# AD.net
KiCad netlist of a schematic drawn in Altium Designer
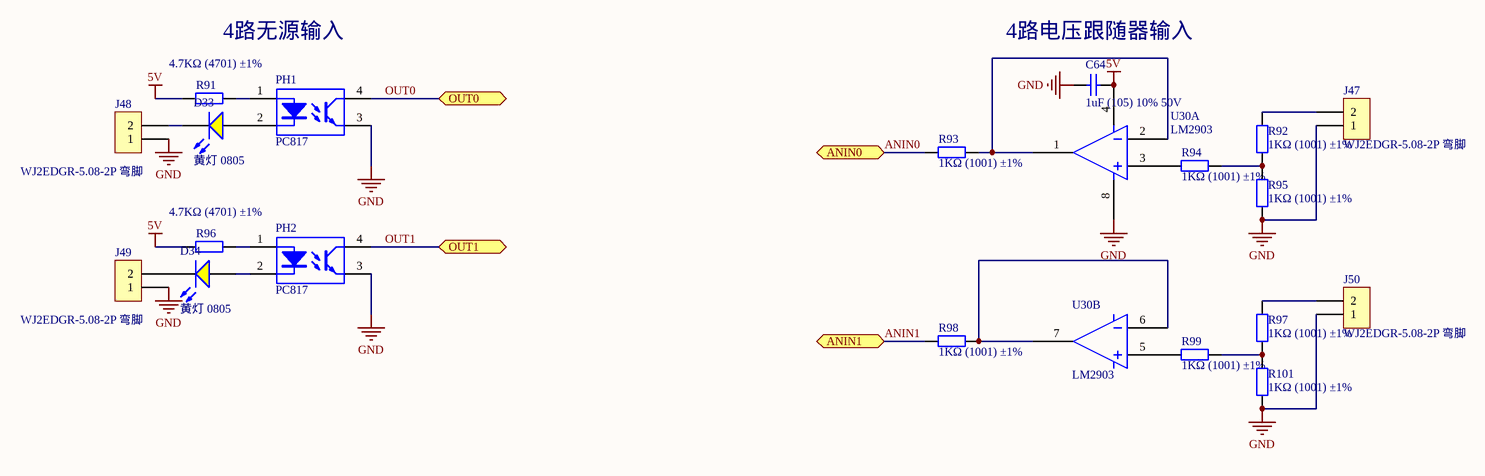
[diagram p0: 光耦输入&AD输入.SchDoc]

(export (version "E")
  (design (tool "Eeschema 10.0.6"))
  (components
    (comp (ref "C64")
      (value "1uF (105) 10% 50V")
      (footprint "0805_C")
      (description "贴片电容")
      (libsource (lib "Cap") (part "0805 1uF (105) 10% 50V"))
    )
    (comp (ref "D33")
      (value "黄灯 0805")
      (footprint "0805_LED_S1")
      (description "发光二极管")
      (libsource (lib "LED") (part "0805 黄灯"))
    )
    (comp (ref "D34")
      (value "黄灯 0805")
      (footprint "0805_LED_S1")
      (description "发光二极管")
      (libsource (lib "LED") (part "0805 黄灯"))
    )
    (comp (ref "J47")
      (value "WJ2EDGR-5.08-2P 弯脚")
      (footprint "Connector:WJ2EDGR-5.08-2")
      (description "2EDG连接器")
      (libsource (lib "Connector") (part "WJ2EDGR-5.08-2P 弯脚"))
    )
    (comp (ref "J48")
      (value "WJ2EDGR-5.08-2P 弯脚")
      (footprint "Connector:WJ2EDGR-5.08-2")
      (description "2EDG连接器")
      (libsource (lib "") (part "WJ2EDGR-5.08-2P 弯脚_1"))
    )
    (comp (ref "J49")
      (value "WJ2EDGR-5.08-2P 弯脚")
      (footprint "Connector:WJ2EDGR-5.08-2")
      (description "2EDG连接器")
      (libsource (lib "") (part "WJ2EDGR-5.08-2P 弯脚_1"))
    )
    (comp (ref "J50")
      (value "WJ2EDGR-5.08-2P 弯脚")
      (footprint "Connector:WJ2EDGR-5.08-2")
      (description "2EDG连接器")
      (libsource (lib "Connector") (part "WJ2EDGR-5.08-2P 弯脚"))
    )
    (comp (ref "PH1")
      (value "PC817")
      (footprint "SOP-4_P2.54")
      (description "Optoisolator")
      (libsource (lib "淘宝封装") (part "PC817"))
    )
    (comp (ref "PH2")
      (value "PC817")
      (footprint "SOP-4_P2.54")
      (description "Optoisolator")
      (libsource (lib "淘宝封装") (part "PC817"))
    )
    (comp (ref "R91")
      (value "4.7KΩ (4701) ±1%")
      (footprint "0805_R")
      (description "贴片电阻")
      (libsource (lib "RES") (part "0805 4.7KΩ (4701) 1%"))
    )
    (comp (ref "R92")
      (value "1KΩ (1001) ±1%")
      (footprint "0805_R")
      (description "贴片电阻")
      (libsource (lib "") (part "0805 1KΩ (1001) 1%_1"))
    )
    (comp (ref "R93")
      (value "1KΩ (1001) ±1%")
      (footprint "0805_R")
      (description "贴片电阻")
      (libsource (lib "RES") (part "0805 1KΩ (1001) 1%"))
    )
    (comp (ref "R94")
      (value "1KΩ (1001) ±1%")
      (footprint "0805_R")
      (description "贴片电阻")
      (libsource (lib "RES") (part "0805 1KΩ (1001) 1%"))
    )
    (comp (ref "R95")
      (value "1KΩ (1001) ±1%")
      (footprint "0805_R")
      (description "贴片电阻")
      (libsource (lib "") (part "0805 1KΩ (1001) 1%_1"))
    )
    (comp (ref "R96")
      (value "4.7KΩ (4701) ±1%")
      (footprint "0805_R")
      (description "贴片电阻")
      (libsource (lib "RES") (part "0805 4.7KΩ (4701) 1%"))
    )
    (comp (ref "R97")
      (value "1KΩ (1001) ±1%")
      (footprint "0805_R")
      (description "贴片电阻")
      (libsource (lib "") (part "0805 1KΩ (1001) 1%_1"))
    )
    (comp (ref "R98")
      (value "1KΩ (1001) ±1%")
      (footprint "0805_R")
      (description "贴片电阻")
      (libsource (lib "RES") (part "0805 1KΩ (1001) 1%"))
    )
    (comp (ref "R99")
      (value "1KΩ (1001) ±1%")
      (footprint "0805_R")
      (description "贴片电阻")
      (libsource (lib "RES") (part "0805 1KΩ (1001) 1%"))
    )
    (comp (ref "R101")
      (value "1KΩ (1001) ±1%")
      (footprint "0805_R")
      (description "贴片电阻")
      (libsource (lib "") (part "0805 1KΩ (1001) 1%_1"))
    )
    (comp (ref "U30") (value "LM2903") (footprint "SOP-8") (libsource (lib "*") (part "LM193")))
  )
  (nets
    (net (code "1") (name "/ANIN0") (class "Default")
      (node (ref "R93") (pin "2") (pinfunction "2_2") (pintype "passive"))
    )
    (net (code "2") (name "/ANIN1") (class "Default")
      (node (ref "R98") (pin "2") (pinfunction "2_2") (pintype "passive"))
    )
    (net (code "3") (name "/OUT0") (class "Default")
      (node (ref "PH1") (pin "4") (pinfunction "C_4") (pintype "passive"))
    )
    (net (code "4") (name "/OUT1") (class "Default")
      (node (ref "PH2") (pin "4") (pinfunction "C_4") (pintype "passive"))
    )
    (net (code "5") (name "5V") (class "Default")
      (node (ref "C64") (pin "2") (pinfunction "2_2") (pintype "passive"))
      (node (ref "R91") (pin "1") (pinfunction "1_1") (pintype "passive"))
      (node (ref "R96") (pin "1") (pinfunction "1_1") (pintype "passive"))
      (node (ref "U30") (pin "4") (pintype "passive"))
    )
    (net (code "6") (name "GND") (class "Default")
      (node (ref "C64") (pin "1") (pinfunction "1_1") (pintype "passive"))
      (node (ref "J47") (pin "1") (pinfunction "1_1") (pintype "passive"))
      (node (ref "J48") (pin "1") (pinfunction "1_1") (pintype "passive"))
      (node (ref "J49") (pin "1") (pinfunction "1_1") (pintype "passive"))
      (node (ref "J50") (pin "1") (pinfunction "1_1") (pintype "passive"))
      (node (ref "PH1") (pin "3") (pinfunction "E_3") (pintype "passive"))
      (node (ref "PH2") (pin "3") (pinfunction "E_3") (pintype "passive"))
      (node (ref "R101") (pin "1") (pinfunction "1_1") (pintype "passive"))
      (node (ref "R95") (pin "1") (pinfunction "1_1") (pintype "passive"))
      (node (ref "U30") (pin "8") (pintype "passive"))
    )
    (net (code "7") (name "Net-(D33-PadK)") (class "Default")
      (node (ref "D33") (pin "K") (pinfunction "K_K") (pintype "passive"))
      (node (ref "J48") (pin "2") (pinfunction "2_2") (pintype "passive"))
    )
    (net (code "8") (name "Net-(D34-PadK)") (class "Default")
      (node (ref "D34") (pin "K") (pinfunction "K_K") (pintype "passive"))
      (node (ref "J49") (pin "2") (pinfunction "2_2") (pintype "passive"))
    )
    (net (code "9") (name "Net-(J47-Pad2)") (class "Default")
      (node (ref "J47") (pin "2") (pinfunction "2_2") (pintype "passive"))
      (node (ref "R92") (pin "2") (pinfunction "2_2") (pintype "passive"))
    )
    (net (code "10") (name "Net-(J50-Pad2)") (class "Default")
      (node (ref "J50") (pin "2") (pinfunction "2_2") (pintype "passive"))
      (node (ref "R97") (pin "2") (pinfunction "2_2") (pintype "passive"))
    )
    (net (code "11") (name "Net-(PH1-A)") (class "Default")
      (node (ref "PH1") (pin "1") (pinfunction "A_1") (pintype "passive"))
      (node (ref "R91") (pin "2") (pinfunction "2_2") (pintype "passive"))
    )
    (net (code "12") (name "Net-(PH1-K)") (class "Default")
      (node (ref "D33") (pin "A") (pinfunction "A_A") (pintype "passive"))
      (node (ref "PH1") (pin "2") (pinfunction "K_2") (pintype "passive"))
    )
    (net (code "13") (name "Net-(PH2-A)") (class "Default")
      (node (ref "PH2") (pin "1") (pinfunction "A_1") (pintype "passive"))
      (node (ref "R96") (pin "2") (pinfunction "2_2") (pintype "passive"))
    )
    (net (code "14") (name "Net-(PH2-K)") (class "Default")
      (node (ref "D34") (pin "A") (pinfunction "A_A") (pintype "passive"))
      (node (ref "PH2") (pin "2") (pinfunction "K_2") (pintype "passive"))
    )
    (net (code "15") (name "Net-(R92-Pad1)") (class "Default")
      (node (ref "R92") (pin "1") (pinfunction "1_1") (pintype "passive"))
      (node (ref "R94") (pin "1") (pinfunction "1_1") (pintype "passive"))
      (node (ref "R95") (pin "2") (pinfunction "2_2") (pintype "passive"))
    )
    (net (code "16") (name "Net-(R93-Pad1)") (class "Default")
      (node (ref "R93") (pin "1") (pinfunction "1_1") (pintype "passive"))
      (node (ref "U30") (pin "1") (pintype "passive"))
      (node (ref "U30") (pin "2") (pintype "passive"))
    )
    (net (code "17") (name "Net-(R94-Pad2)") (class "Default")
      (node (ref "R94") (pin "2") (pinfunction "2_2") (pintype "passive"))
      (node (ref "U30") (pin "3") (pintype "passive"))
    )
    (net (code "18") (name "Net-(R98-Pad1)") (class "Default")
      (node (ref "R98") (pin "1") (pinfunction "1_1") (pintype "passive"))
      (node (ref "U30") (pin "6") (pintype "passive"))
      (node (ref "U30") (pin "7") (pintype "passive"))
    )
    (net (code "19") (name "Net-(R99-Pad2)") (class "Default")
      (node (ref "R99") (pin "2") (pinfunction "2_2") (pintype "passive"))
      (node (ref "U30") (pin "5") (pintype "passive"))
    )
    (net (code "20") (name "Net-(R101-Pad2)") (class "Default")
      (node (ref "R101") (pin "2") (pinfunction "2_2") (pintype "passive"))
      (node (ref "R97") (pin "1") (pinfunction "1_1") (pintype "passive"))
      (node (ref "R99") (pin "1") (pinfunction "1_1") (pintype "passive"))
    )
  )
)
